# MSSRP-USER_IF.net
KiCad netlist of a schematic drawn in EAGLE
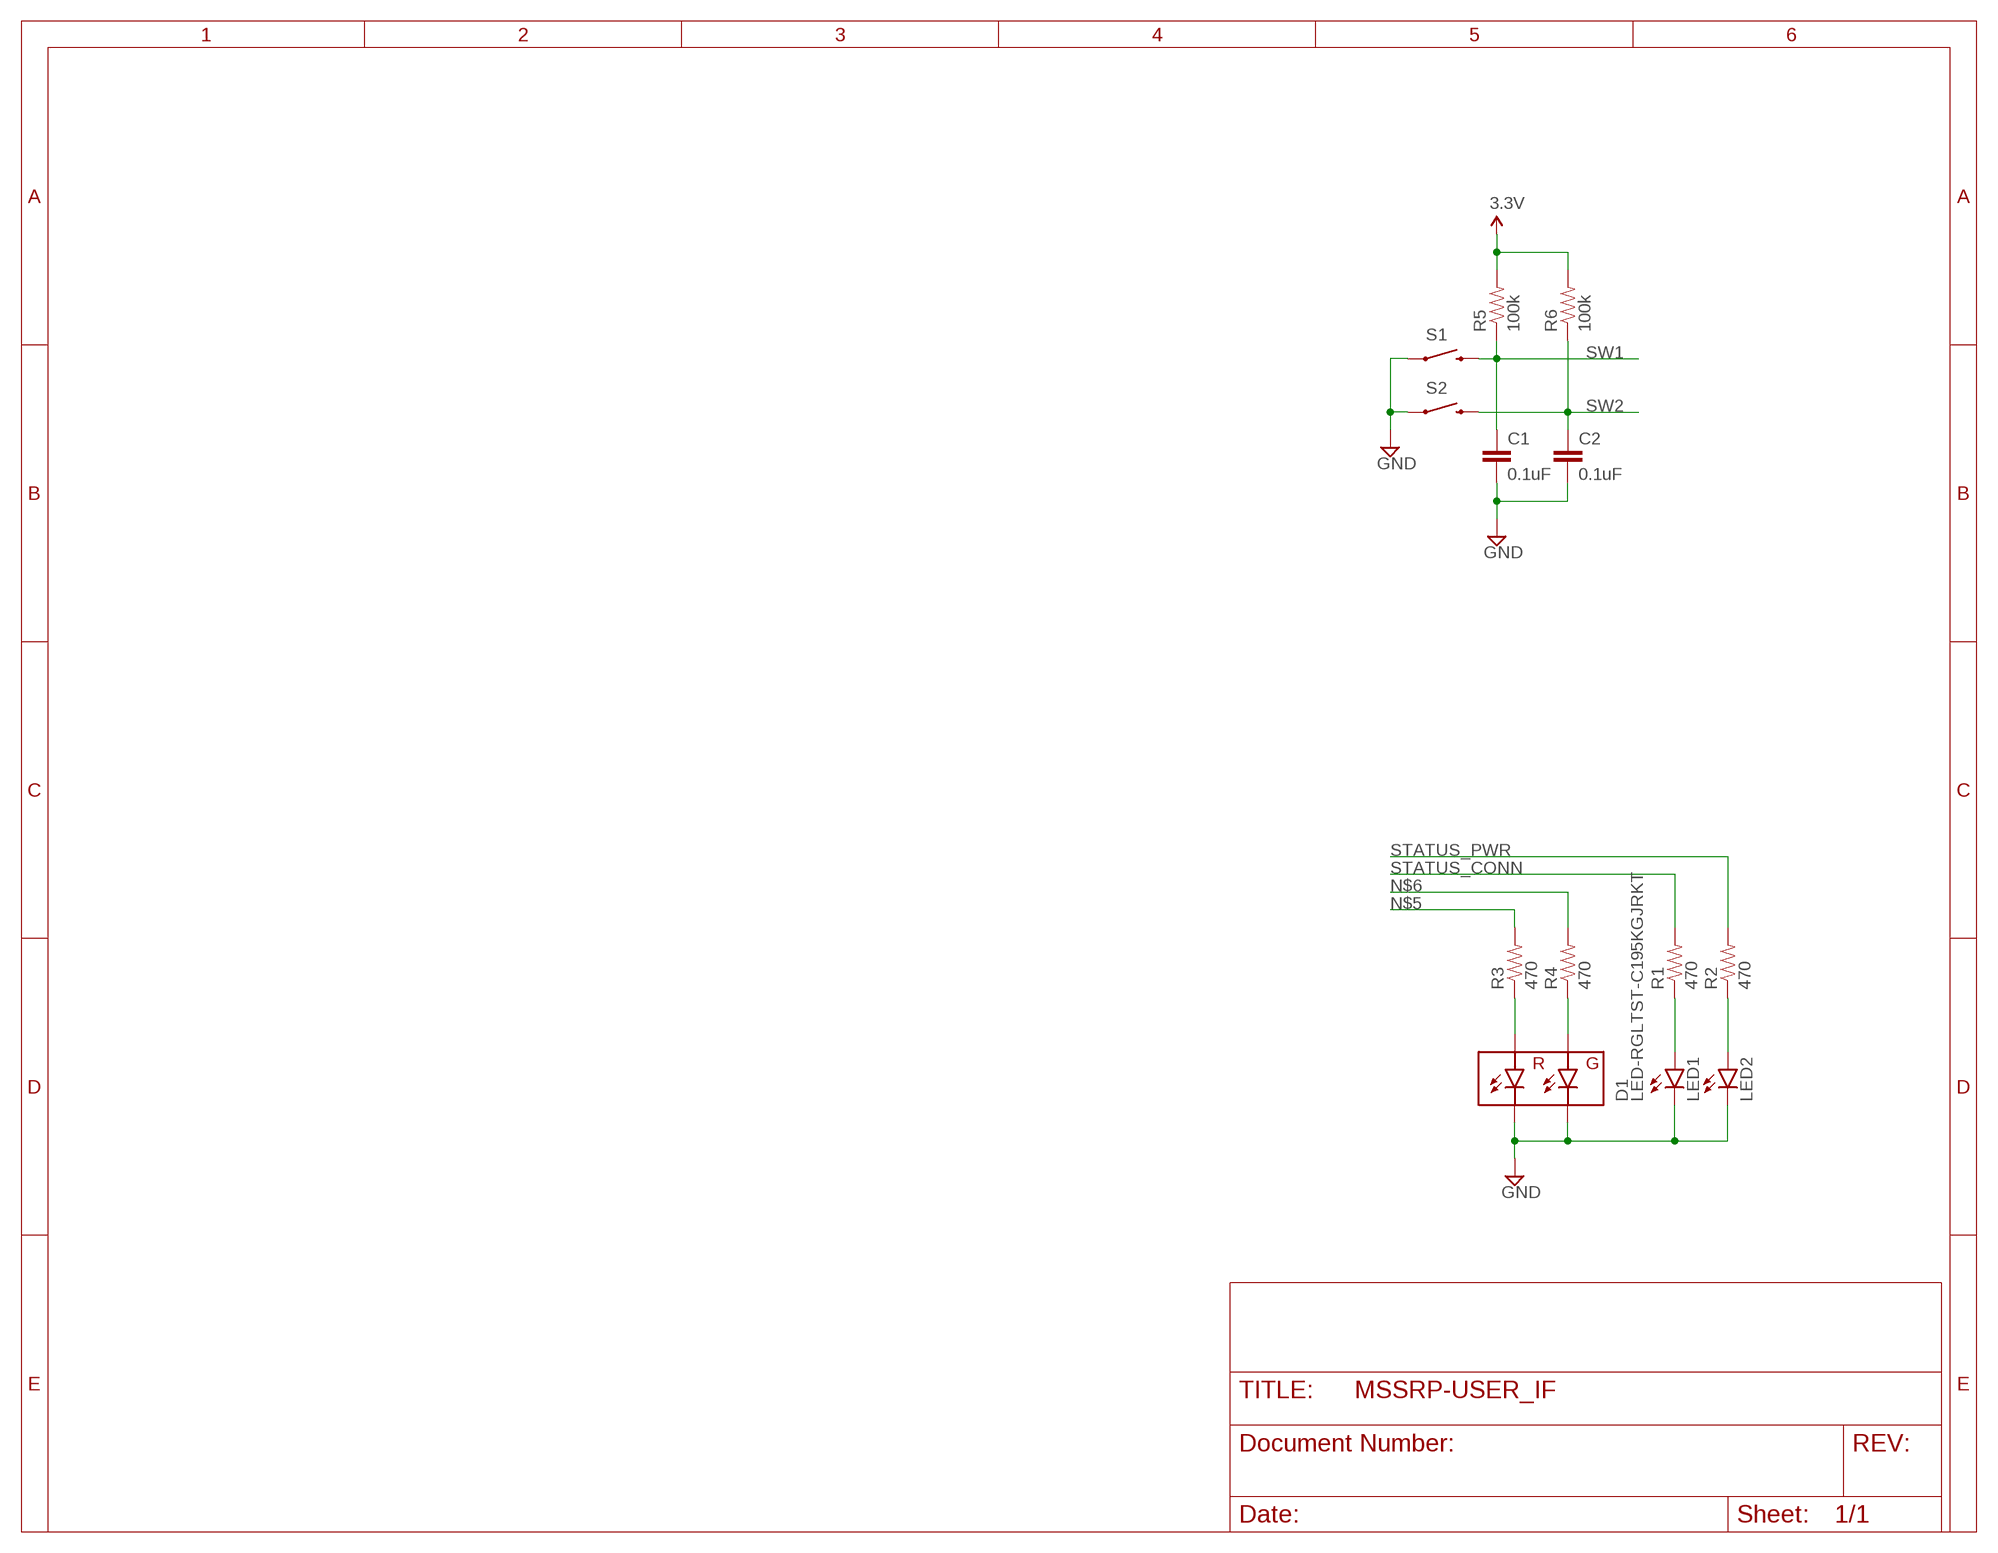
[diagram p0: schematic, sheet 1]

(export (version "E")
  (design (tool "Eeschema 10.0.6"))
  (components
    (comp (ref "C1")
      (value "0.1uF")
      (footprint "eagle-import:0603-CAP")
      (libsource (lib "eagle-import") (part "0.1UF-25V-5%(0603)"))
    )
    (comp (ref "C2")
      (value "0.1uF")
      (footprint "eagle-import:0603-CAP")
      (libsource (lib "eagle-import") (part "0.1UF-25V-5%(0603)"))
    )
    (comp (ref "D1")
      (value "LED-RGLTST-C195KGJRKT")
      (footprint "eagle-import:LTST-C195KGJRKT")
      (libsource (lib "eagle-import") (part "LED-RGLTST-C195KGJRKT"))
    )
    (comp (ref "LED1")
      (value "LED0603")
      (footprint "eagle-import:LED-0603")
      (libsource (lib "eagle-import") (part "LED0603"))
    )
    (comp (ref "LED2")
      (value "LED0603")
      (footprint "eagle-import:LED-0603")
      (libsource (lib "eagle-import") (part "LED0603"))
    )
    (comp (ref "R1")
      (value "470")
      (footprint "eagle-import:0603-RES")
      (libsource (lib "eagle-import") (part "470OHM1/10W1%(0603)"))
    )
    (comp (ref "R2")
      (value "470")
      (footprint "eagle-import:0603-RES")
      (libsource (lib "eagle-import") (part "470OHM1/10W1%(0603)"))
    )
    (comp (ref "R3")
      (value "470")
      (footprint "eagle-import:0603-RES")
      (libsource (lib "eagle-import") (part "470OHM1/10W1%(0603)"))
    )
    (comp (ref "R4")
      (value "470")
      (footprint "eagle-import:0603-RES")
      (libsource (lib "eagle-import") (part "470OHM1/10W1%(0603)"))
    )
    (comp (ref "R5")
      (value "100k")
      (footprint "eagle-import:0603-RES")
      (libsource (lib "eagle-import") (part "100KOHM1/10W1%(0603)"))
    )
    (comp (ref "R6")
      (value "100k")
      (footprint "eagle-import:0603-RES")
      (libsource (lib "eagle-import") (part "100KOHM1/10W1%(0603)"))
    )
    (comp (ref "S1")
      (value "SWITCH-MOMENTARY-2-SMD-1101NE")
      (footprint "eagle-import:TACTILE-SWITCH-1101NE")
      (libsource (lib "eagle-import") (part "SWITCH-MOMENTARY-2-SMD-1101NE"))
    )
    (comp (ref "S2")
      (value "SWITCH-MOMENTARY-2-SMD-1101NE")
      (footprint "eagle-import:TACTILE-SWITCH-1101NE")
      (libsource (lib "eagle-import") (part "SWITCH-MOMENTARY-2-SMD-1101NE"))
    )
  )
  (nets
    (net (code "1") (name "/N$5") (class "Default")
      (node (ref "R3") (pin "2") (pinfunction "2_2") (pintype "passive"))
    )
    (net (code "2") (name "/N$6") (class "Default")
      (node (ref "R4") (pin "2") (pinfunction "2_2") (pintype "passive"))
    )
    (net (code "3") (name "/STATUS_CONN") (class "Default")
      (node (ref "R1") (pin "2") (pinfunction "2_2") (pintype "passive"))
    )
    (net (code "4") (name "/STATUS_PWR") (class "Default")
      (node (ref "R2") (pin "2") (pinfunction "2_2") (pintype "passive"))
    )
    (net (code "5") (name "/SW1") (class "Default")
      (node (ref "C1") (pin "1") (pinfunction "1_1") (pintype "passive"))
      (node (ref "R5") (pin "1") (pinfunction "1_1") (pintype "passive"))
      (node (ref "S1") (pin "P$2") (pinfunction "2_P$2") (pintype "passive"))
    )
    (net (code "6") (name "/SW2") (class "Default")
      (node (ref "C2") (pin "1") (pinfunction "1_1") (pintype "passive"))
      (node (ref "R6") (pin "1") (pinfunction "1_1") (pintype "passive"))
      (node (ref "S2") (pin "P$2") (pinfunction "2_P$2") (pintype "passive"))
    )
    (net (code "7") (name "3.3V") (class "Default")
      (node (ref "R5") (pin "2") (pinfunction "2_2") (pintype "passive"))
      (node (ref "R6") (pin "2") (pinfunction "2_2") (pintype "passive"))
    )
    (net (code "8") (name "GND") (class "Default")
      (node (ref "C1") (pin "2") (pinfunction "2_2") (pintype "passive"))
      (node (ref "C2") (pin "2") (pinfunction "2_2") (pintype "passive"))
      (node (ref "D1") (pin "P$3") (pinfunction "GC_P$3") (pintype "passive"))
      (node (ref "D1") (pin "P$4") (pinfunction "RC_P$4") (pintype "passive"))
      (node (ref "LED1") (pin "C") (pinfunction "C_C") (pintype "passive"))
      (node (ref "LED2") (pin "C") (pinfunction "C_C") (pintype "passive"))
      (node (ref "S1") (pin "P$1") (pinfunction "1_P$1") (pintype "passive"))
      (node (ref "S2") (pin "P$1") (pinfunction "1_P$1") (pintype "passive"))
    )
    (net (code "9") (name "Net-(D1-GA)") (class "Default")
      (node (ref "D1") (pin "P$1") (pinfunction "GA_P$1") (pintype "passive"))
      (node (ref "R4") (pin "1") (pinfunction "1_1") (pintype "passive"))
    )
    (net (code "10") (name "Net-(D1-RA)") (class "Default")
      (node (ref "D1") (pin "P$2") (pinfunction "RA_P$2") (pintype "passive"))
      (node (ref "R3") (pin "1") (pinfunction "1_1") (pintype "passive"))
    )
    (net (code "11") (name "Net-(LED1-PadA)") (class "Default")
      (node (ref "LED1") (pin "A") (pinfunction "A_A") (pintype "passive"))
      (node (ref "R1") (pin "1") (pinfunction "1_1") (pintype "passive"))
    )
    (net (code "12") (name "Net-(LED2-PadA)") (class "Default")
      (node (ref "LED2") (pin "A") (pinfunction "A_A") (pintype "passive"))
      (node (ref "R2") (pin "1") (pinfunction "1_1") (pintype "passive"))
    )
  )
)
